# monoastavel-cascateando-astavel.net
KiCad netlist of a schematic drawn in EAGLE
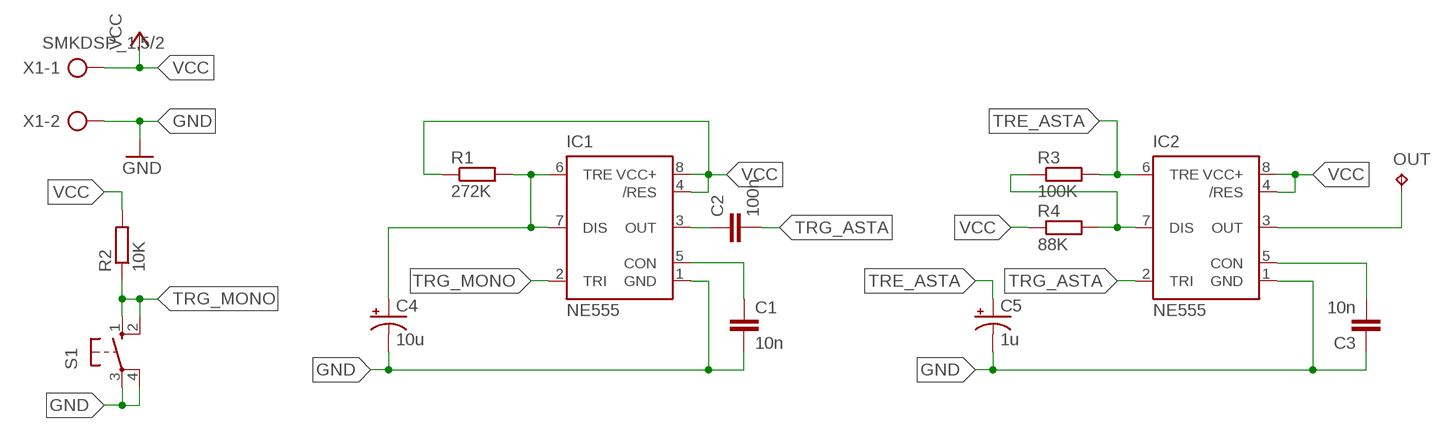
[diagram p0: schematic, sheet 1]

(export (version "E")
  (design (tool "Eeschema 10.0.6"))
  (components
    (comp (ref "C1")
      (value "10n")
      (footprint "eagle-import:C2.5-2")
      (libsource (lib "eagle-import") (part "C2.5/2"))
    )
    (comp (ref "C2")
      (value "100n")
      (footprint "eagle-import:C2.5-2")
      (libsource (lib "eagle-import") (part "C2.5/2"))
    )
    (comp (ref "C3")
      (value "10n")
      (footprint "eagle-import:C2.5-2")
      (libsource (lib "eagle-import") (part "C2.5/2"))
    )
    (comp (ref "C4")
      (value "10u")
      (footprint "eagle-import:TAP5-60")
      (libsource (lib "eagle-import") (part "CPOL-USTAP5-60"))
    )
    (comp (ref "C5")
      (value "1u")
      (footprint "eagle-import:TAP5-60")
      (libsource (lib "eagle-import") (part "CPOL-USTAP5-60"))
    )
    (comp (ref "IC1")
      (value "NE555")
      (footprint "eagle-import:DIL-08")
      (fields (field (name "MF") "Arrow Electronics") (field (name "MPN") "NE555N"))
      (libsource (lib "eagle-import") (part "NE555"))
    )
    (comp (ref "IC2")
      (value "NE555")
      (footprint "eagle-import:DIL-08")
      (fields (field (name "MF") "Arrow Electronics") (field (name "MPN") "NE555N"))
      (libsource (lib "eagle-import") (part "NE555"))
    )
    (comp (ref "OUT")
      (value "TPPAD1-13")
      (footprint "eagle-import:P1-13")
      (libsource (lib "eagle-import") (part "TPPAD1-13"))
    )
    (comp (ref "R1")
      (value "272K")
      (footprint "eagle-import:0207_10")
      (libsource (lib "eagle-import") (part "R-EU_0207/10"))
    )
    (comp (ref "R2")
      (value "10K")
      (footprint "eagle-import:0207_10")
      (libsource (lib "eagle-import") (part "R-EU_0207/10"))
    )
    (comp (ref "R3")
      (value "100K")
      (footprint "eagle-import:0207_10")
      (libsource (lib "eagle-import") (part "R-EU_0207/10"))
    )
    (comp (ref "R4")
      (value "88K")
      (footprint "eagle-import:0207_10")
      (libsource (lib "eagle-import") (part "R-EU_0207/10"))
    )
    (comp (ref "S1")
      (value "10-XX")
      (footprint "eagle-import:B3F-10XX")
      (fields (field (name "MPN") "B3F-1000"))
      (libsource (lib "eagle-import") (part "10-XX"))
    )
    (comp (ref "X1")
      (value "SMKDSP_1,5/2")
      (footprint "eagle-import:SMKDSP_1,5_2")
      (fields (field (name "MF") "FARNELL") (field (name "MPN") "1733570"))
      (libsource (lib "eagle-import") (part "SMKDSP_1,5/2"))
    )
  )
  (nets
    (net (code "1") (name "GND") (class "Default")
      (node (ref "C1") (pin "2") (pinfunction "2_2") (pintype "passive"))
      (node (ref "C3") (pin "1") (pinfunction "1_1") (pintype "passive"))
      (node (ref "C4") (pin "-") (pinfunction "-_-") (pintype "passive"))
      (node (ref "C5") (pin "-") (pinfunction "-_-") (pintype "passive"))
      (node (ref "IC1") (pin "1") (pinfunction "GND_1") (pintype "power_in"))
      (node (ref "IC2") (pin "1") (pinfunction "GND_1") (pintype "power_in"))
      (node (ref "S1") (pin "3") (pinfunction "P_3") (pintype "passive"))
      (node (ref "S1") (pin "4") (pinfunction "P1_4") (pintype "passive"))
      (node (ref "X1") (pin "2") (pinfunction "KL_2") (pintype "passive"))
    )
    (net (code "2") (name "Net-(IC1-CON)") (class "Default")
      (node (ref "C1") (pin "1") (pinfunction "1_1") (pintype "passive"))
      (node (ref "IC1") (pin "5") (pinfunction "CON_5") (pintype "input"))
    )
    (net (code "3") (name "Net-(IC1-DIS)") (class "Default")
      (node (ref "C4") (pin "+") (pinfunction "+_+") (pintype "passive"))
      (node (ref "IC1") (pin "6") (pinfunction "TRE_6") (pintype "input"))
      (node (ref "IC1") (pin "7") (pinfunction "DIS_7") (pintype "input"))
      (node (ref "R1") (pin "2") (pinfunction "2_2") (pintype "passive"))
    )
    (net (code "4") (name "Net-(IC1-OUT)") (class "Default")
      (node (ref "C2") (pin "1") (pinfunction "1_1") (pintype "passive"))
      (node (ref "IC1") (pin "3") (pinfunction "OUT_3") (pintype "output"))
    )
    (net (code "5") (name "Net-(IC2-CON)") (class "Default")
      (node (ref "C3") (pin "2") (pinfunction "2_2") (pintype "passive"))
      (node (ref "IC2") (pin "5") (pinfunction "CON_5") (pintype "input"))
    )
    (net (code "6") (name "Net-(IC2-DIS)") (class "Default")
      (node (ref "IC2") (pin "7") (pinfunction "DIS_7") (pintype "input"))
      (node (ref "R3") (pin "1") (pinfunction "1_1") (pintype "passive"))
      (node (ref "R4") (pin "2") (pinfunction "2_2") (pintype "passive"))
    )
    (net (code "7") (name "Net-(IC2-OUT)") (class "Default")
      (node (ref "IC2") (pin "3") (pinfunction "OUT_3") (pintype "output"))
      (node (ref "OUT") (pin "TP") (pinfunction "TP_TP") (pintype "input"))
    )
    (net (code "8") (name "TRE_ASTA") (class "Default")
      (node (ref "C5") (pin "+") (pinfunction "+_+") (pintype "passive"))
      (node (ref "IC2") (pin "6") (pinfunction "TRE_6") (pintype "input"))
      (node (ref "R3") (pin "2") (pinfunction "2_2") (pintype "passive"))
    )
    (net (code "9") (name "TRG_ASTA") (class "Default")
      (node (ref "C2") (pin "2") (pinfunction "2_2") (pintype "passive"))
      (node (ref "IC2") (pin "2") (pinfunction "TRI_2") (pintype "input"))
    )
    (net (code "10") (name "TRG_MONO") (class "Default")
      (node (ref "IC1") (pin "2") (pinfunction "TRI_2") (pintype "input"))
      (node (ref "R2") (pin "1") (pinfunction "1_1") (pintype "passive"))
      (node (ref "S1") (pin "1") (pinfunction "S_1") (pintype "passive"))
      (node (ref "S1") (pin "2") (pinfunction "S1_2") (pintype "passive"))
    )
    (net (code "11") (name "VCC") (class "Default")
      (node (ref "IC1") (pin "4") (pinfunction "/RES_4") (pintype "input"))
      (node (ref "IC1") (pin "8") (pinfunction "VCC+_8") (pintype "power_in"))
      (node (ref "IC2") (pin "4") (pinfunction "/RES_4") (pintype "input"))
      (node (ref "IC2") (pin "8") (pinfunction "VCC+_8") (pintype "power_in"))
      (node (ref "R1") (pin "1") (pinfunction "1_1") (pintype "passive"))
      (node (ref "R2") (pin "2") (pinfunction "2_2") (pintype "passive"))
      (node (ref "R4") (pin "1") (pinfunction "1_1") (pintype "passive"))
      (node (ref "X1") (pin "1") (pinfunction "KL_1") (pintype "passive"))
    )
  )
)
